# Audio_Input_Mic_In.net
KiCad netlist of a schematic drawn in Altium Designer
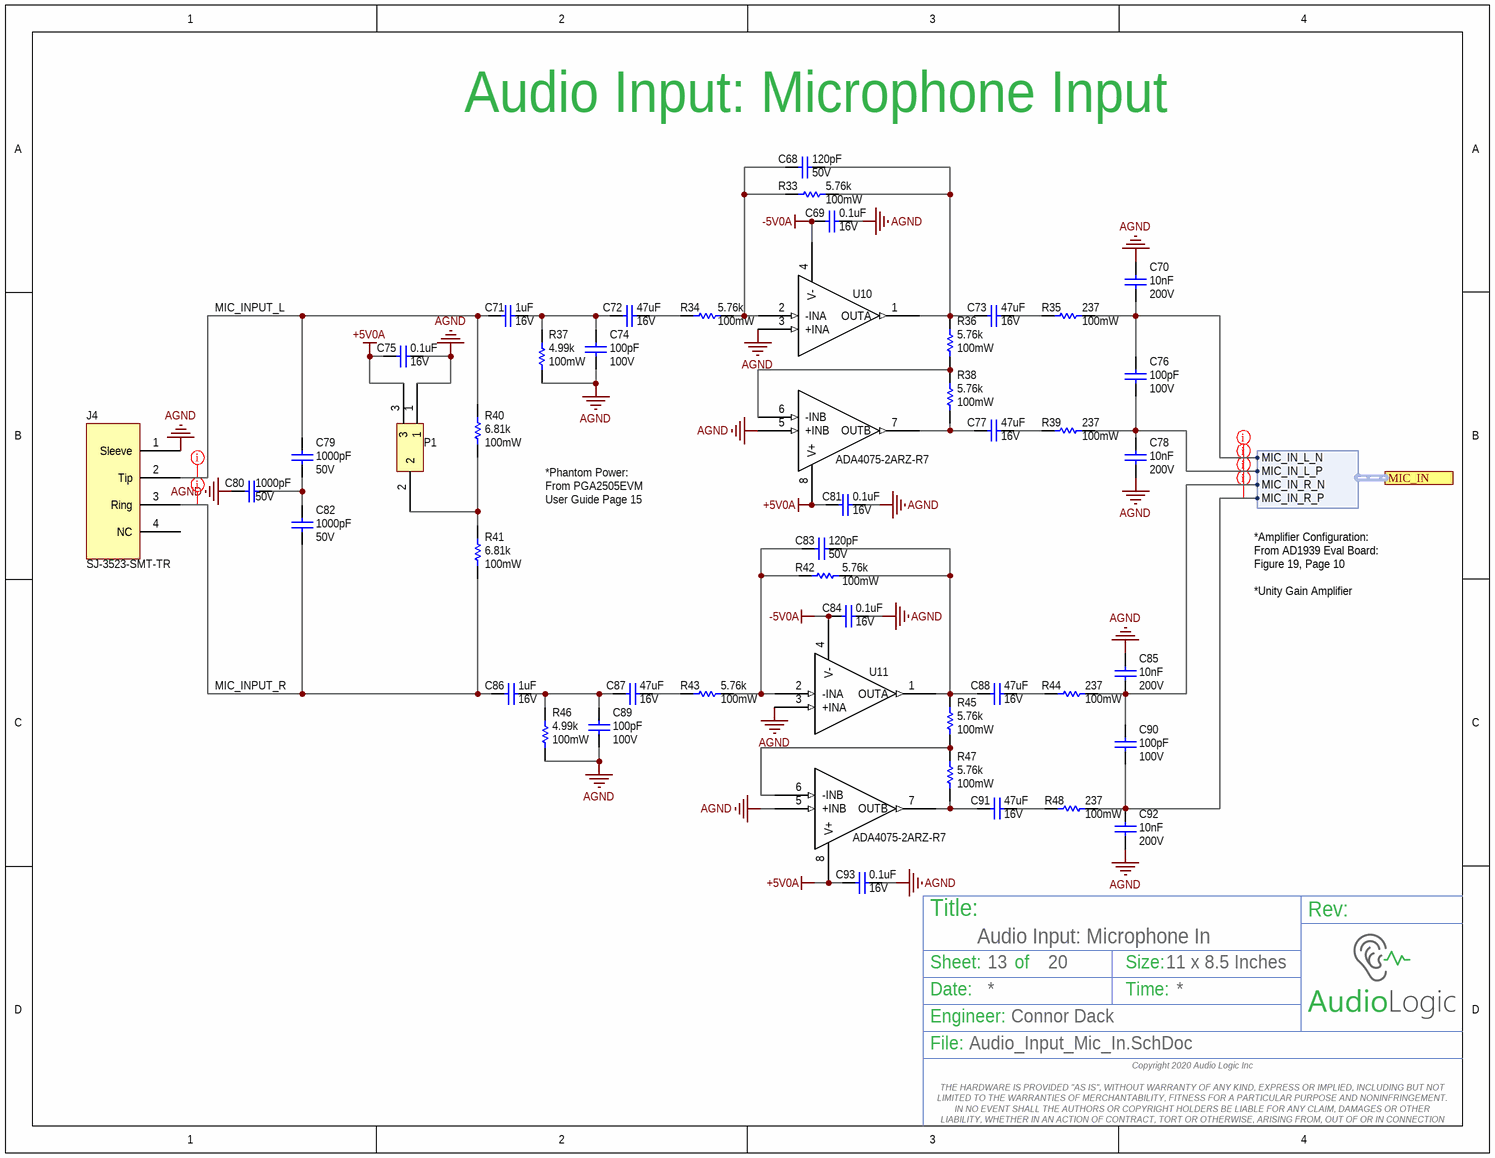
[diagram p0: Audio_Input_Mic_In.SchDoc]

(export (version "E")
  (design (tool "Eeschema 10.0.6"))
  (components
    (comp (ref "C68")
      (value "CL10C121JB8NCNC")
      (footprint "3-0603_L")
      (description "120pF 50V Ceramic Capacitor C0G, NP0 0603 (1608 Metric) 0.063\" L x 0.031\" W (1.60mm x 0.80mm)")
      (fields
        (field (name "MANUFACTURER") "Samsung Electro-Mechanics America, Inc.")
        (field (name "TOLERANCE") "±5%")
        (field (name "VOLTAGE - RATED") "50V")
        (field (name "CAPACITANCE") "120pF")
      )
      (libsource (lib "Schematic_Components") (part "CL10C121JB8NCNC"))
    )
    (comp (ref "C69")
      (value "CL10F104ZO8NNNC")
      (footprint "3-0603_L")
      (description "CAP CER 0.1UF 16V Y5V 0603")
      (fields
        (field (name "MANUFACTURER") "Samsung")
        (field (name "TOLERANCE") "80%")
        (field (name "VOLTAGE RATING") "16V")
        (field (name "CAPACITANCE") "0.1uF")
      )
      (libsource (lib "Schematic_Components_CD") (part "CL10F104ZO8NNNC"))
    )
    (comp (ref "C70")
      (value "~")
      (footprint "3-0603_L")
      (description "CAP CER 10000PF 200V X7R 0603")
      (fields
        (field (name "MANUFACTURER") "KEMET")
        (field (name "MANUFACTURER PART NUMBER") "C0603C103J2RACTU")
        (field (name "VOLTAGE RATING") "200V")
        (field (name "CAPACITANCE") "10nF")
      )
      (libsource (lib "Miscellaneous Devices") (part "C0603C103J2RACTU"))
    )
    (comp (ref "C71")
      (value "CGA3E1X7R1C105M080AC")
      (footprint "3-0603_L")
      (description "CAP CER 1UF 16V X7R 0603")
      (fields
        (field (name "MANUFACTURER") "TDK")
        (field (name "TOLERANCE") "20%")
        (field (name "VOLTAGE RATING") "16V")
        (field (name "CAPACITANCE") "1uF")
      )
      (libsource (lib "Schematic_Components_CD") (part "CGA3E1X7R1C105M080AC"))
    )
    (comp (ref "C72")
      (value "CL32A476KOJNNNE")
      (footprint "C1210X25_L")
      (description "CAP CER 47UF 16V X5R 1210")
      (fields
        (field (name "MANUFACTURER") "Samsung")
        (field (name "TOLERANCE") "10%")
        (field (name "VOLTAGE RATING") "16V")
        (field (name "CAPACITANCE") "47uF")
      )
      (libsource (lib "Schematic_Components_CD") (part "CL32A476KOJNNNE"))
    )
    (comp (ref "C73")
      (value "CL32A476KOJNNNE")
      (footprint "C1210X25_L")
      (description "CAP CER 47UF 16V X5R 1210")
      (fields
        (field (name "MANUFACTURER") "Samsung")
        (field (name "TOLERANCE") "10%")
        (field (name "VOLTAGE RATING") "16V")
        (field (name "CAPACITANCE") "47uF")
      )
      (libsource (lib "Schematic_Components_CD") (part "CL32A476KOJNNNE"))
    )
    (comp (ref "C74")
      (value "C1608C0G2A101J")
      (footprint "3-0603_L")
      (description "CAP CER 100PF 100V 5% NP0 0603")
      (fields
        (field (name "MANUFACTURER") "TDK Corporation")
        (field (name "VOLTAGE - RATED") "100V")
        (field (name "TOLERANCE") "±5%")
        (field (name "CAPACITANCE") "100pF")
      )
      (libsource (lib "Schematic_Components") (part "C1608C0G2A101J"))
    )
    (comp (ref "C75")
      (value "CL10F104ZO8NNNC")
      (footprint "3-0603_L")
      (description "CAP CER 0.1UF 16V Y5V 0603")
      (fields
        (field (name "MANUFACTURER") "Samsung")
        (field (name "TOLERANCE") "80%")
        (field (name "VOLTAGE RATING") "16V")
        (field (name "CAPACITANCE") "0.1uF")
      )
      (libsource (lib "Schematic_Components_CD") (part "CL10F104ZO8NNNC"))
    )
    (comp (ref "C76")
      (value "C1608C0G2A101J")
      (footprint "3-0603_L")
      (description "CAP CER 100PF 100V 5% NP0 0603")
      (fields
        (field (name "MANUFACTURER") "TDK Corporation")
        (field (name "VOLTAGE - RATED") "100V")
        (field (name "TOLERANCE") "±5%")
        (field (name "CAPACITANCE") "100pF")
      )
      (libsource (lib "Schematic_Components") (part "C1608C0G2A101J"))
    )
    (comp (ref "C77")
      (value "CL32A476KOJNNNE")
      (footprint "C1210X25_L")
      (description "CAP CER 47UF 16V X5R 1210")
      (fields
        (field (name "MANUFACTURER") "Samsung")
        (field (name "TOLERANCE") "10%")
        (field (name "VOLTAGE RATING") "16V")
        (field (name "CAPACITANCE") "47uF")
      )
      (libsource (lib "Schematic_Components_CD") (part "CL32A476KOJNNNE"))
    )
    (comp (ref "C78")
      (value "~")
      (footprint "3-0603_L")
      (description "CAP CER 10000PF 200V X7R 0603")
      (fields
        (field (name "MANUFACTURER") "KEMET")
        (field (name "MANUFACTURER PART NUMBER") "C0603C103J2RACTU")
        (field (name "VOLTAGE RATING") "200V")
        (field (name "CAPACITANCE") "10nF")
      )
      (libsource (lib "Miscellaneous Devices") (part "C0603C103J2RACTU"))
    )
    (comp (ref "C79")
      (value "CL10B102KB8NNNC")
      (footprint "3-0603_L")
      (description "1000pF 50V Ceramic Capacitor X7R 0603 (1608 Metric) 0.063\" L x 0.031\" W (1.60mm x 0.80mm)")
      (fields
        (field (name "MANUFACTURER") "Samsung Electro-Mechanics America, Inc.")
        (field (name "TOLERANCE") "±10%")
        (field (name "VOLTAGE - RATED") "50V")
        (field (name "CAPACITANCE") "1000pF")
      )
      (libsource (lib "Schematic_Components") (part "CL10B102KB8NNNC"))
    )
    (comp (ref "C80")
      (value "CL10B102KB8NNNC")
      (footprint "3-0603_L")
      (description "1000pF 50V Ceramic Capacitor X7R 0603 (1608 Metric) 0.063\" L x 0.031\" W (1.60mm x 0.80mm)")
      (fields
        (field (name "MANUFACTURER") "Samsung Electro-Mechanics America, Inc.")
        (field (name "TOLERANCE") "±10%")
        (field (name "VOLTAGE - RATED") "50V")
        (field (name "CAPACITANCE") "1000pF")
      )
      (libsource (lib "Schematic_Components") (part "CL10B102KB8NNNC"))
    )
    (comp (ref "C81")
      (value "CL10F104ZO8NNNC")
      (footprint "3-0603_L")
      (description "CAP CER 0.1UF 16V Y5V 0603")
      (fields
        (field (name "MANUFACTURER") "Samsung")
        (field (name "TOLERANCE") "80%")
        (field (name "VOLTAGE RATING") "16V")
        (field (name "CAPACITANCE") "0.1uF")
      )
      (libsource (lib "Schematic_Components_CD") (part "CL10F104ZO8NNNC"))
    )
    (comp (ref "C82")
      (value "CL10B102KB8NNNC")
      (footprint "3-0603_L")
      (description "1000pF 50V Ceramic Capacitor X7R 0603 (1608 Metric) 0.063\" L x 0.031\" W (1.60mm x 0.80mm)")
      (fields
        (field (name "MANUFACTURER") "Samsung Electro-Mechanics America, Inc.")
        (field (name "TOLERANCE") "±10%")
        (field (name "VOLTAGE - RATED") "50V")
        (field (name "CAPACITANCE") "1000pF")
      )
      (libsource (lib "Schematic_Components") (part "CL10B102KB8NNNC"))
    )
    (comp (ref "C83")
      (value "CL10C121JB8NCNC")
      (footprint "3-0603_L")
      (description "120pF 50V Ceramic Capacitor C0G, NP0 0603 (1608 Metric) 0.063\" L x 0.031\" W (1.60mm x 0.80mm)")
      (fields
        (field (name "MANUFACTURER") "Samsung Electro-Mechanics America, Inc.")
        (field (name "TOLERANCE") "±5%")
        (field (name "VOLTAGE - RATED") "50V")
        (field (name "CAPACITANCE") "120pF")
      )
      (libsource (lib "Schematic_Components") (part "CL10C121JB8NCNC"))
    )
    (comp (ref "C84")
      (value "CL10F104ZO8NNNC")
      (footprint "3-0603_L")
      (description "CAP CER 0.1UF 16V Y5V 0603")
      (fields
        (field (name "MANUFACTURER") "Samsung")
        (field (name "TOLERANCE") "80%")
        (field (name "VOLTAGE RATING") "16V")
        (field (name "CAPACITANCE") "0.1uF")
      )
      (libsource (lib "Schematic_Components_CD") (part "CL10F104ZO8NNNC"))
    )
    (comp (ref "C85")
      (value "~")
      (footprint "3-0603_L")
      (description "CAP CER 10000PF 200V X7R 0603")
      (fields
        (field (name "MANUFACTURER") "KEMET")
        (field (name "MANUFACTURER PART NUMBER") "C0603C103J2RACTU")
        (field (name "VOLTAGE RATING (DC)") "200V")
        (field (name "CAPACITANCE") "10nF")
      )
      (libsource (lib "Miscellaneous Devices") (part "C0603C103J2RACTU"))
    )
    (comp (ref "C86")
      (value "CGA3E1X7R1C105M080AC")
      (footprint "3-0603_L")
      (description "CAP CER 1UF 16V X7R 0603")
      (fields
        (field (name "MANUFACTURER") "TDK")
        (field (name "TOLERANCE") "20%")
        (field (name "VOLTAGE RATING") "16V")
        (field (name "CAPACITANCE") "1uF")
      )
      (libsource (lib "Schematic_Components_CD") (part "CGA3E1X7R1C105M080AC"))
    )
    (comp (ref "C87")
      (value "CL32A476KOJNNNE")
      (footprint "C1210X25_L")
      (description "CAP CER 47UF 16V X5R 1210")
      (fields
        (field (name "MANUFACTURER") "Samsung")
        (field (name "TOLERANCE") "10%")
        (field (name "VOLTAGE RATING") "16V")
        (field (name "CAPACITANCE") "47uF")
      )
      (libsource (lib "Schematic_Components_CD") (part "CL32A476KOJNNNE"))
    )
    (comp (ref "C88")
      (value "CL32A476KOJNNNE")
      (footprint "C1210X25_L")
      (description "CAP CER 47UF 16V X5R 1210")
      (fields
        (field (name "MANUFACTURER") "Samsung")
        (field (name "TOLERANCE") "10%")
        (field (name "VOLTAGE RATING") "16V")
        (field (name "CAPACITANCE") "47uF")
      )
      (libsource (lib "Schematic_Components_CD") (part "CL32A476KOJNNNE"))
    )
    (comp (ref "C89")
      (value "C1608C0G2A101J")
      (footprint "3-0603_L")
      (description "CAP CER 100PF 100V 5% NP0 0603")
      (fields
        (field (name "MANUFACTURER") "TDK Corporation")
        (field (name "VOLTAGE - RATED") "100V")
        (field (name "TOLERANCE") "±5%")
        (field (name "CAPACITANCE") "100pF")
      )
      (libsource (lib "Schematic_Components") (part "C1608C0G2A101J"))
    )
    (comp (ref "C90")
      (value "C1608C0G2A101J")
      (footprint "3-0603_L")
      (description "CAP CER 100PF 100V 5% NP0 0603")
      (fields
        (field (name "MANUFACTURER") "TDK Corporation")
        (field (name "VOLTAGE - RATED") "100V")
        (field (name "TOLERANCE") "±5%")
        (field (name "CAPACITANCE") "100pF")
      )
      (libsource (lib "Schematic_Components") (part "C1608C0G2A101J"))
    )
    (comp (ref "C91")
      (value "CL32A476KOJNNNE")
      (footprint "C1210X25_L")
      (description "CAP CER 47UF 16V X5R 1210")
      (fields
        (field (name "MANUFACTURER") "Samsung")
        (field (name "TOLERANCE") "10%")
        (field (name "VOLTAGE RATING") "16V")
        (field (name "CAPACITANCE") "47uF")
      )
      (libsource (lib "Schematic_Components_CD") (part "CL32A476KOJNNNE"))
    )
    (comp (ref "C92")
      (value "~")
      (footprint "3-0603_L")
      (description "CAP CER 10000PF 200V X7R 0603")
      (fields
        (field (name "MANUFACTURER") "KEMET")
        (field (name "MANUFACTURER PART NUMBER") "C0603C103J2RACTU")
        (field (name "VOLTAGE RATING") "200V")
        (field (name "CAPACITANCE") "10nF")
      )
      (libsource (lib "Miscellaneous Devices") (part "C0603C103J2RACTU"))
    )
    (comp (ref "C93")
      (value "CL10F104ZO8NNNC")
      (footprint "3-0603_L")
      (description "CAP CER 0.1UF 16V Y5V 0603")
      (fields
        (field (name "MANUFACTURER") "Samsung")
        (field (name "TOLERANCE") "80%")
        (field (name "VOLTAGE RATING") "16V")
        (field (name "CAPACITANCE") "0.1uF")
      )
      (libsource (lib "Schematic_Components_CD") (part "CL10F104ZO8NNNC"))
    )
    (comp (ref "J4")
      (value "SJ-3523-SMT-TR")
      (footprint "SJ-3523-SMT-TR")
      (description "3.50mm (0.141\", 1/8\", Mini Plug) - Headphone Phone Jack Stereo Connector Solder")
      (fields
        (field (name "MANUFACTURER") "CUI Inc.")
        (field (name "MANUFACTURER PART NUMBER") "SJ-3523-SMT-TR")
        (field (name "PUBLISHER") "Altium Limited")
      )
      (libsource (lib "NIH_DE0_Nano_Daughter_Card_Library") (part "SJ-3523-SMT-TR"))
    )
    (comp (ref "P1")
      (value "3PIN_Connector")
      (footprint "3Pin_Header")
      (description "3 Pin Through Hole Connector with 0.1\" Spacing")
      (fields
        (field (name "MANUFACTURER") "Samtec")
        (field (name "MANUFACTURER PART NUMBER") "TSW-103-07-G-S")
        (field (name "PUBLISHER") "Altium Limited")
      )
      (libsource (lib "Schematic_Components_CD") (part "CONN_TH_3PIN_0D1"))
    )
    (comp (ref "R33")
      (value "ERJ-3EKF5761V")
      (footprint "3-0603_R_L")
      (description "RES SMD 5.76K OHM 1% 1/10W 0603")
      (fields
        (field (name "MANUFACTURER") "Panasonic Electronic Components")
        (field (name "TOLERANCE") "±1%")
        (field (name "POWER (WATTS)") "100mW")
        (field (name "RESISTANCE (OHMS)") "5.76k")
      )
      (libsource (lib "Schematic_Components") (part "ERJ-3EKF5761V"))
    )
    (comp (ref "R34")
      (value "ERJ-3EKF5761V")
      (footprint "3-0603_R_L")
      (description "RES SMD 5.76K OHM 1% 1/10W 0603")
      (fields
        (field (name "MANUFACTURER") "Panasonic Electronic Components")
        (field (name "TOLERANCE") "±1%")
        (field (name "POWER (WATTS)") "100mW")
        (field (name "RESISTANCE (OHMS)") "5.76k")
      )
      (libsource (lib "Schematic_Components") (part "ERJ-3EKF5761V"))
    )
    (comp (ref "R35")
      (value "ERJ-3EKF2370V")
      (footprint "3-0603_R_L")
      (description "RES SMD 237 OHM 1% 1/10W 0603")
      (fields
        (field (name "MANUFACTURER") "Panasonic Electronic Components")
        (field (name "TOLERANCE") "±1%")
        (field (name "POWER (WATTS)") "100mW")
        (field (name "RESISTANCE (OHMS)") "237")
      )
      (libsource (lib "Schematic_Components") (part "ERJ-3EKF2370V"))
    )
    (comp (ref "R36")
      (value "ERJ-3EKF5761V")
      (footprint "3-0603_R_L")
      (description "RES SMD 5.76K OHM 1% 1/10W 0603")
      (fields
        (field (name "MANUFACTURER") "Panasonic Electronic Components")
        (field (name "TOLERANCE") "±1%")
        (field (name "POWER (WATTS)") "100mW")
        (field (name "RESISTANCE (OHMS)") "5.76k")
      )
      (libsource (lib "Schematic_Components") (part "ERJ-3EKF5761V"))
    )
    (comp (ref "R37")
      (value "ERJ-3EKF4991V")
      (footprint "3-0603_R_L")
      (description "RES SMD 4.99K OHM 1% 1/10W 0603")
      (fields
        (field (name "MANUFACTURER") "Panasonic Electronic Components")
        (field (name "TOLERANCE") "±1%")
        (field (name "POWER (WATTS)") "100mW")
        (field (name "RESISTANCE (OHMS)") "4.99k")
      )
      (libsource (lib "Schematic_Components") (part "ERJ-3EKF4991V"))
    )
    (comp (ref "R38")
      (value "ERJ-3EKF5761V")
      (footprint "3-0603_R_L")
      (description "RES SMD 5.76K OHM 1% 1/10W 0603")
      (fields
        (field (name "MANUFACTURER") "Panasonic Electronic Components")
        (field (name "TOLERANCE") "±1%")
        (field (name "POWER (WATTS)") "100mW")
        (field (name "RESISTANCE (OHMS)") "5.76k")
      )
      (libsource (lib "Schematic_Components") (part "ERJ-3EKF5761V"))
    )
    (comp (ref "R39")
      (value "ERJ-3EKF2370V")
      (footprint "3-0603_R_L")
      (description "RES SMD 237 OHM 1% 1/10W 0603")
      (fields
        (field (name "MANUFACTURER") "Panasonic Electronic Components")
        (field (name "TOLERANCE") "±1%")
        (field (name "POWER (WATTS)") "100mW")
        (field (name "RESISTANCE (OHMS)") "237")
      )
      (libsource (lib "Schematic_Components") (part "ERJ-3EKF2370V"))
    )
    (comp (ref "R40")
      (value "ERJ-3EKF6811V")
      (footprint "3-0603_R_L")
      (description "RES SMD 6.81K OHM 1% 1/10W 0603")
      (fields
        (field (name "MANUFACTURER") "Panasonic ECG")
        (field (name "TOLERANCE") "1%")
        (field (name "POWER RATING") "100mW")
        (field (name "RESISTANCE") "6.81k")
      )
      (libsource (lib "Schematic_Components_CD") (part "ERJ-3EKF6811V"))
    )
    (comp (ref "R41")
      (value "ERJ-3EKF6811V")
      (footprint "3-0603_R_L")
      (description "RES SMD 6.81K OHM 1% 1/10W 0603")
      (fields
        (field (name "MANUFACTURER") "Panasonic ECG")
        (field (name "TOLERANCE") "1%")
        (field (name "POWER RATING") "100mW")
        (field (name "RESISTANCE") "6.81k")
      )
      (libsource (lib "Schematic_Components_CD") (part "ERJ-3EKF6811V"))
    )
    (comp (ref "R42")
      (value "ERJ-3EKF5761V")
      (footprint "3-0603_R_L")
      (description "RES SMD 5.76K OHM 1% 1/10W 0603")
      (fields
        (field (name "MANUFACTURER") "Panasonic Electronic Components")
        (field (name "TOLERANCE") "±1%")
        (field (name "POWER (WATTS)") "100mW")
        (field (name "RESISTANCE (OHMS)") "5.76k")
      )
      (libsource (lib "Schematic_Components") (part "ERJ-3EKF5761V"))
    )
    (comp (ref "R43")
      (value "ERJ-3EKF5761V")
      (footprint "3-0603_R_L")
      (description "RES SMD 5.76K OHM 1% 1/10W 0603")
      (fields
        (field (name "MANUFACTURER") "Panasonic Electronic Components")
        (field (name "TOLERANCE") "±1%")
        (field (name "POWER (WATTS)") "100mW")
        (field (name "RESISTANCE (OHMS)") "5.76k")
      )
      (libsource (lib "Schematic_Components") (part "ERJ-3EKF5761V"))
    )
    (comp (ref "R44")
      (value "ERJ-3EKF2370V")
      (footprint "3-0603_R_L")
      (description "RES SMD 237 OHM 1% 1/10W 0603")
      (fields
        (field (name "MANUFACTURER") "Panasonic Electronic Components")
        (field (name "TOLERANCE") "±1%")
        (field (name "POWER (WATTS)") "100mW")
        (field (name "RESISTANCE (OHMS)") "237")
      )
      (libsource (lib "Schematic_Components") (part "ERJ-3EKF2370V"))
    )
    (comp (ref "R45")
      (value "ERJ-3EKF5761V")
      (footprint "3-0603_R_L")
      (description "RES SMD 5.76K OHM 1% 1/10W 0603")
      (fields
        (field (name "MANUFACTURER") "Panasonic Electronic Components")
        (field (name "TOLERANCE") "±1%")
        (field (name "POWER (WATTS)") "100mW")
        (field (name "RESISTANCE (OHMS)") "5.76k")
      )
      (libsource (lib "Schematic_Components") (part "ERJ-3EKF5761V"))
    )
    (comp (ref "R46")
      (value "ERJ-3EKF4991V")
      (footprint "3-0603_R_L")
      (description "RES SMD 4.99K OHM 1% 1/10W 0603")
      (fields
        (field (name "MANUFACTURER") "Panasonic Electronic Components")
        (field (name "TOLERANCE") "±1%")
        (field (name "POWER (WATTS)") "100mW")
        (field (name "RESISTANCE (OHMS)") "4.99k")
      )
      (libsource (lib "Schematic_Components") (part "ERJ-3EKF4991V"))
    )
    (comp (ref "R47")
      (value "ERJ-3EKF5761V")
      (footprint "3-0603_R_L")
      (description "RES SMD 5.76K OHM 1% 1/10W 0603")
      (fields
        (field (name "MANUFACTURER") "Panasonic Electronic Components")
        (field (name "TOLERANCE") "±1%")
        (field (name "POWER (WATTS)") "100mW")
        (field (name "RESISTANCE (OHMS)") "5.76k")
      )
      (libsource (lib "Schematic_Components") (part "ERJ-3EKF5761V"))
    )
    (comp (ref "R48")
      (value "ERJ-3EKF2370V")
      (footprint "3-0603_R_L")
      (description "RES SMD 237 OHM 1% 1/10W 0603")
      (fields
        (field (name "MANUFACTURER") "Panasonic Electronic Components")
        (field (name "TOLERANCE") "±1%")
        (field (name "POWER (WATTS)") "100mW")
        (field (name "RESISTANCE (OHMS)") "237")
      )
      (libsource (lib "Schematic_Components") (part "ERJ-3EKF2370V"))
    )
    (comp (ref "U10")
      (value "ADA4075-2ARZ-R7")
      (footprint "SOIC127P600X175-8L")
      (description "IC OPAMP GP 6.5MHZ 8SOIC")
      (fields
        (field (name "MANUFACTURER") "Analog Devices Inc.")
        (field (name "MANUFACTURER PART NUMBER") "ADA4075-2ARZ-R7")
      )
      (libsource (lib "Schematic_Components_CD") (part "ADA4075-2ARZ-R7"))
    )
    (comp (ref "U11")
      (value "ADA4075-2ARZ-R7")
      (footprint "SOIC127P600X175-8L")
      (description "IC OPAMP GP 6.5MHZ 8SOIC")
      (fields
        (field (name "MANUFACTURER") "Analog Devices Inc.")
        (field (name "MANUFACTURER PART NUMBER") "ADA4075-2ARZ-R7")
      )
      (libsource (lib "Schematic_Components_CD") (part "ADA4075-2ARZ-R7"))
    )
  )
  (nets
    (net (code "2") (name "+5V0A") (class "Default")
      (node (ref "C75") (pin "2") (pinfunction "2_2") (pintype "passive"))
      (node (ref "C81") (pin "2") (pinfunction "2_2") (pintype "passive"))
      (node (ref "C93") (pin "2") (pinfunction "2_2") (pintype "passive"))
      (node (ref "P1") (pin "3") (pinfunction "3_3") (pintype "passive"))
      (node (ref "U10") (pin "8") (pinfunction "V+_8") (pintype "passive"))
      (node (ref "U11") (pin "8") (pinfunction "V+_8") (pintype "passive"))
    )
    (net (code "3") (name "-5V0A") (class "Default")
      (node (ref "C69") (pin "2") (pinfunction "2_2") (pintype "passive"))
      (node (ref "C84") (pin "2") (pinfunction "2_2") (pintype "passive"))
      (node (ref "U10") (pin "4") (pinfunction "V-_4") (pintype "passive"))
      (node (ref "U11") (pin "4") (pinfunction "V-_4") (pintype "passive"))
    )
    (net (code "4") (name "/MIC_INPUT_L") (class "Default")
      (node (ref "C71") (pin "1") (pinfunction "1_1") (pintype "passive"))
      (node (ref "C79") (pin "2") (pinfunction "2_2") (pintype "passive"))
      (node (ref "J4") (pin "2") (pinfunction "Tip_2") (pintype "passive"))
      (node (ref "R40") (pin "2") (pinfunction "2_2") (pintype "passive"))
    )
    (net (code "5") (name "/MIC_INPUT_R") (class "Default")
      (node (ref "C82") (pin "1") (pinfunction "1_1") (pintype "passive"))
      (node (ref "C86") (pin "1") (pinfunction "1_1") (pintype "passive"))
      (node (ref "J4") (pin "3") (pinfunction "Ring_3") (pintype "passive"))
      (node (ref "R41") (pin "1") (pinfunction "1_1") (pintype "passive"))
    )
    (net (code "7") (name "AGND") (class "Default")
      (node (ref "C69") (pin "1") (pinfunction "1_1") (pintype "passive"))
      (node (ref "C70") (pin "2") (pinfunction "2_2") (pintype "passive"))
      (node (ref "C74") (pin "2") (pinfunction "2_2") (pintype "passive"))
      (node (ref "C75") (pin "1") (pinfunction "1_1") (pintype "passive"))
      (node (ref "C78") (pin "1") (pinfunction "1_1") (pintype "passive"))
      (node (ref "C80") (pin "2") (pinfunction "2_2") (pintype "passive"))
      (node (ref "C81") (pin "1") (pinfunction "1_1") (pintype "passive"))
      (node (ref "C84") (pin "1") (pinfunction "1_1") (pintype "passive"))
      (node (ref "C85") (pin "2") (pinfunction "2_2") (pintype "passive"))
      (node (ref "C89") (pin "2") (pinfunction "2_2") (pintype "passive"))
      (node (ref "C92") (pin "1") (pinfunction "1_1") (pintype "passive"))
      (node (ref "C93") (pin "1") (pinfunction "1_1") (pintype "passive"))
      (node (ref "J4") (pin "1") (pinfunction "Sleeve_1") (pintype "passive"))
      (node (ref "P1") (pin "1") (pinfunction "1_1") (pintype "passive"))
      (node (ref "R37") (pin "1") (pinfunction "1_1") (pintype "passive"))
      (node (ref "R46") (pin "1") (pinfunction "1_1") (pintype "passive"))
      (node (ref "U10") (pin "3") (pinfunction "+INA_3") (pintype "input"))
      (node (ref "U10") (pin "5") (pinfunction "+INB_5") (pintype "input"))
      (node (ref "U11") (pin "3") (pinfunction "+INA_3") (pintype "input"))
      (node (ref "U11") (pin "5") (pinfunction "+INB_5") (pintype "input"))
    )
    (net (code "8") (name "Net-(C70-Pad1)") (class "Default")
      (node (ref "C70") (pin "1") (pinfunction "1_1") (pintype "passive"))
      (node (ref "C76") (pin "2") (pinfunction "2_2") (pintype "passive"))
      (node (ref "R35") (pin "2") (pinfunction "2_2") (pintype "passive"))
    )
    (net (code "9") (name "Net-(C71-Pad2)") (class "Default")
      (node (ref "C71") (pin "2") (pinfunction "2_2") (pintype "passive"))
      (node (ref "C72") (pin "1") (pinfunction "1_1") (pintype "passive"))
      (node (ref "C74") (pin "1") (pinfunction "1_1") (pintype "passive"))
      (node (ref "R37") (pin "2") (pinfunction "2_2") (pintype "passive"))
    )
    (net (code "10") (name "Net-(C72-Pad2)") (class "Default")
      (node (ref "C72") (pin "2") (pinfunction "2_2") (pintype "passive"))
      (node (ref "R34") (pin "1") (pinfunction "1_1") (pintype "passive"))
    )
    (net (code "11") (name "Net-(C73-Pad2)") (class "Default")
      (node (ref "C73") (pin "2") (pinfunction "2_2") (pintype "passive"))
      (node (ref "R35") (pin "1") (pinfunction "1_1") (pintype "passive"))
    )
    (net (code "12") (name "Net-(C76-Pad1)") (class "Default")
      (node (ref "C76") (pin "1") (pinfunction "1_1") (pintype "passive"))
      (node (ref "C78") (pin "2") (pinfunction "2_2") (pintype "passive"))
      (node (ref "R39") (pin "2") (pinfunction "2_2") (pintype "passive"))
    )
    (net (code "13") (name "Net-(C77-Pad2)") (class "Default")
      (node (ref "C77") (pin "2") (pinfunction "2_2") (pintype "passive"))
      (node (ref "R39") (pin "1") (pinfunction "1_1") (pintype "passive"))
    )
    (net (code "14") (name "Net-(C79-Pad1)") (class "Default")
      (node (ref "C79") (pin "1") (pinfunction "1_1") (pintype "passive"))
      (node (ref "C80") (pin "1") (pinfunction "1_1") (pintype "passive"))
      (node (ref "C82") (pin "2") (pinfunction "2_2") (pintype "passive"))
    )
    (net (code "15") (name "Net-(C85-Pad1)") (class "Default")
      (node (ref "C85") (pin "1") (pinfunction "1_1") (pintype "passive"))
      (node (ref "C90") (pin "2") (pinfunction "2_2") (pintype "passive"))
      (node (ref "R44") (pin "2") (pinfunction "2_2") (pintype "passive"))
    )
    (net (code "16") (name "Net-(C86-Pad2)") (class "Default")
      (node (ref "C86") (pin "2") (pinfunction "2_2") (pintype "passive"))
      (node (ref "C87") (pin "1") (pinfunction "1_1") (pintype "passive"))
      (node (ref "C89") (pin "1") (pinfunction "1_1") (pintype "passive"))
      (node (ref "R46") (pin "2") (pinfunction "2_2") (pintype "passive"))
    )
    (net (code "17") (name "Net-(C87-Pad2)") (class "Default")
      (node (ref "C87") (pin "2") (pinfunction "2_2") (pintype "passive"))
      (node (ref "R43") (pin "1") (pinfunction "1_1") (pintype "passive"))
    )
    (net (code "18") (name "Net-(C88-Pad2)") (class "Default")
      (node (ref "C88") (pin "2") (pinfunction "2_2") (pintype "passive"))
      (node (ref "R44") (pin "1") (pinfunction "1_1") (pintype "passive"))
    )
    (net (code "19") (name "Net-(C90-Pad1)") (class "Default")
      (node (ref "C90") (pin "1") (pinfunction "1_1") (pintype "passive"))
      (node (ref "C92") (pin "2") (pinfunction "2_2") (pintype "passive"))
      (node (ref "R48") (pin "2") (pinfunction "2_2") (pintype "passive"))
    )
    (net (code "20") (name "Net-(C91-Pad2)") (class "Default")
      (node (ref "C91") (pin "2") (pinfunction "2_2") (pintype "passive"))
      (node (ref "R48") (pin "1") (pinfunction "1_1") (pintype "passive"))
    )
    (net (code "21") (name "Net-(P1-Pad2)") (class "Default")
      (node (ref "P1") (pin "2") (pinfunction "2_2") (pintype "passive"))
      (node (ref "R40") (pin "1") (pinfunction "1_1") (pintype "passive"))
      (node (ref "R41") (pin "2") (pinfunction "2_2") (pintype "passive"))
    )
    (net (code "22") (name "Net-(U10--INA)") (class "Default")
      (node (ref "C68") (pin "1") (pinfunction "1_1") (pintype "passive"))
      (node (ref "R33") (pin "1") (pinfunction "1_1") (pintype "passive"))
      (node (ref "R34") (pin "2") (pinfunction "2_2") (pintype "passive"))
      (node (ref "U10") (pin "2") (pinfunction "-INA_2") (pintype "input"))
    )
    (net (code "23") (name "Net-(U10--INB)") (class "Default")
      (node (ref "R36") (pin "2") (pinfunction "2_2") (pintype "passive"))
      (node (ref "R38") (pin "1") (pinfunction "1_1") (pintype "passive"))
      (node (ref "U10") (pin "6") (pinfunction "-INB_6") (pintype "input"))
    )
    (net (code "24") (name "Net-(U10-OUTA)") (class "Default")
      (node (ref "C68") (pin "2") (pinfunction "2_2") (pintype "passive"))
      (node (ref "C73") (pin "1") (pinfunction "1_1") (pintype "passive"))
      (node (ref "R33") (pin "2") (pinfunction "2_2") (pintype "passive"))
      (node (ref "R36") (pin "1") (pinfunction "1_1") (pintype "passive"))
      (node (ref "U10") (pin "1") (pinfunction "OUTA_1") (pintype "output"))
    )
    (net (code "25") (name "Net-(U10-OUTB)") (class "Default")
      (node (ref "C77") (pin "1") (pinfunction "1_1") (pintype "passive"))
      (node (ref "R38") (pin "2") (pinfunction "2_2") (pintype "passive"))
      (node (ref "U10") (pin "7") (pinfunction "OUTB_7") (pintype "output"))
    )
    (net (code "26") (name "Net-(U11--INA)") (class "Default")
      (node (ref "C83") (pin "1") (pinfunction "1_1") (pintype "passive"))
      (node (ref "R42") (pin "1") (pinfunction "1_1") (pintype "passive"))
      (node (ref "R43") (pin "2") (pinfunction "2_2") (pintype "passive"))
      (node (ref "U11") (pin "2") (pinfunction "-INA_2") (pintype "input"))
    )
    (net (code "27") (name "Net-(U11--INB)") (class "Default")
      (node (ref "R45") (pin "2") (pinfunction "2_2") (pintype "passive"))
      (node (ref "R47") (pin "1") (pinfunction "1_1") (pintype "passive"))
      (node (ref "U11") (pin "6") (pinfunction "-INB_6") (pintype "input"))
    )
    (net (code "28") (name "Net-(U11-OUTA)") (class "Default")
      (node (ref "C83") (pin "2") (pinfunction "2_2") (pintype "passive"))
      (node (ref "C88") (pin "1") (pinfunction "1_1") (pintype "passive"))
      (node (ref "R42") (pin "2") (pinfunction "2_2") (pintype "passive"))
      (node (ref "R45") (pin "1") (pinfunction "1_1") (pintype "passive"))
      (node (ref "U11") (pin "1") (pinfunction "OUTA_1") (pintype "output"))
    )
    (net (code "29") (name "Net-(U11-OUTB)") (class "Default")
      (node (ref "C91") (pin "1") (pinfunction "1_1") (pintype "passive"))
      (node (ref "R47") (pin "2") (pinfunction "2_2") (pintype "passive"))
      (node (ref "U11") (pin "7") (pinfunction "OUTB_7") (pintype "output"))
    )
    (net (code "30") (name "unconnected-(J4-NC-Pad4)") (class "Default")
      (node (ref "J4") (pin "4") (pinfunction "NC_4") (pintype "passive"))
    )
  )
)
